# USB_UART.net
KiCad netlist of a schematic drawn in Altium Designer
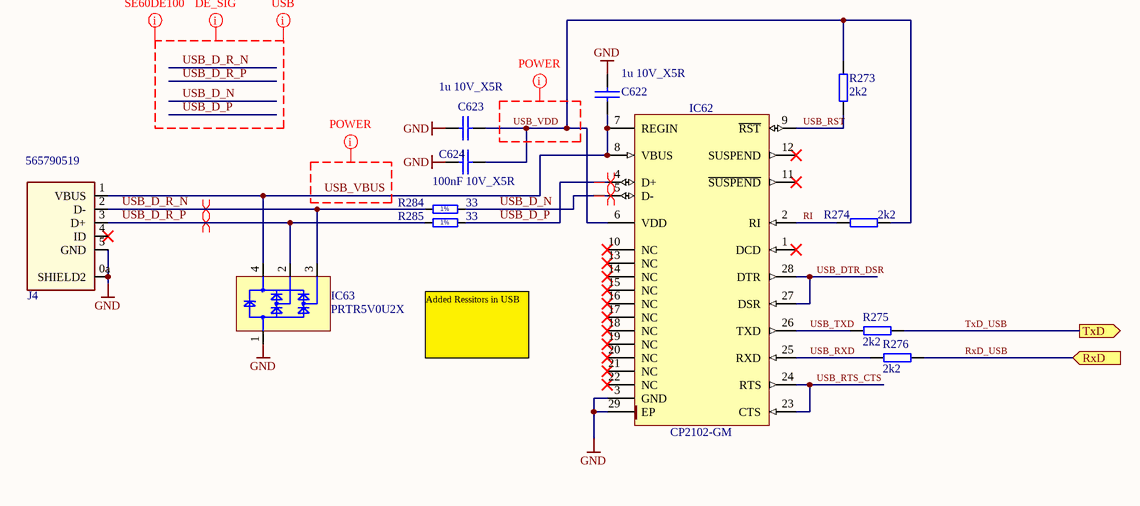
[diagram p0: USB_UART.SchDoc]

(export (version "E")
  (design (tool "Eeschema 10.0.6"))
  (components
    (comp (ref "C622")
      (value "1u 10V_X5R")
      (footprint "0603C")
      (description "Capacitor SMD")
      (libsource (lib "LIBRARY_SCH") (part "CAP_SMD_0603"))
    )
    (comp (ref "C623")
      (value "1u 10V_X5R")
      (footprint "0603C")
      (description "Capacitor SMD")
      (libsource (lib "LIBRARY_SCH") (part "CAP_SMD_0603"))
    )
    (comp (ref "C624")
      (value "100nF 10V_X5R")
      (footprint "0402C")
      (description "Capacitor SMD")
      (libsource (lib "LIBRARY_SCH") (part "CAP_SMD_0402"))
    )
    (comp (ref "IC62")
      (value "CP2102-GM")
      (footprint "QFN50P500X500X100-29N-S335")
      (description "Single-Chip USB to UART Bridge")
      (fields (field (name "MANUFACTURER") "SILICON LABS") (field (name "AUTHOR") "CERN DEM JLC"))
      (libsource (lib "ICs And Semiconductors") (part "CP2102-GM"))
    )
    (comp (ref "IC63")
      (value "PRTR5V0U2X")
      (footprint "sot143b")
      (description "dual 5.5 ESD transient voltage suppressor")
      (libsource (lib "LIBRARY_SCH") (part "D_TVS_PRTR5V0U2X"))
    )
    (comp (ref "J4")
      (value "565790519")
      (footprint "CON_USB_565790519")
      (description "USB mini B connector (Molex)")
      (fields (field (name "PART NUMBER") "10133"))
      (libsource (lib "LIBRARY_SCH") (part "CON_USB_B_MINI_TH"))
    )
    (comp (ref "R273")
      (value "2k2")
      (footprint "0402R")
      (description "SMD Resistor")
      (libsource (lib "LIBRARY_SCH") (part "RES_0402"))
    )
    (comp (ref "R274")
      (value "2k2")
      (footprint "0402R")
      (description "SMD Resistor")
      (libsource (lib "LIBRARY_SCH") (part "RES_0402"))
    )
    (comp (ref "R275")
      (value "2k2")
      (footprint "0402R")
      (description "SMD Resistor")
      (libsource (lib "LIBRARY_SCH") (part "RES_0402"))
    )
    (comp (ref "R276")
      (value "2k2")
      (footprint "0402R")
      (description "SMD Resistor")
      (libsource (lib "LIBRARY_SCH") (part "RES_0402"))
    )
    (comp (ref "R284")
      (value "33")
      (footprint "RESC1005X40N")
      (description "Resistor - 1%")
      (fields
        (field (name "PART NUMBER") "R0402_33R_1%_0.0625W_100PPM")
        (field (name "POWER") "0.0625W")
        (field (name "AUTHOR") "CERN DEM JLC")
      )
      (libsource (lib "Resistors") (part "Resistor - 1%"))
    )
    (comp (ref "R285")
      (value "33")
      (footprint "RESC1005X40N")
      (description "Resistor - 1%")
      (fields
        (field (name "PART NUMBER") "R0402_33R_1%_0.0625W_100PPM")
        (field (name "POWER") "0.0625W")
        (field (name "AUTHOR") "CERN DEM JLC")
      )
      (libsource (lib "Resistors") (part "Resistor - 1%"))
    )
  )
  (nets
    (net (code "1") (name "/RI") (class "Default")
      (node (ref "IC62") (pin "2") (pinfunction "RI_2") (pintype "input"))
      (node (ref "R274") (pin "1") (pinfunction "1_1") (pintype "passive"))
    )
    (net (code "2") (name "/RxD_USB") (class "Default")
      (node (ref "R276") (pin "1") (pinfunction "1_1") (pintype "passive"))
    )
    (net (code "3") (name "/TxD_USB") (class "Default")
      (node (ref "R275") (pin "1") (pinfunction "1_1") (pintype "passive"))
    )
    (net (code "4") (name "/USB_DTR_DSR") (class "Default")
      (node (ref "IC62") (pin "27") (pinfunction "DSR_27") (pintype "input"))
      (node (ref "IC62") (pin "28") (pinfunction "DTR_28") (pintype "output"))
    )
    (net (code "5") (name "/USB_D_N") (class "Default")
      (node (ref "IC62") (pin "5") (pinfunction "D-_5") (pintype "bidirectional"))
      (node (ref "R284") (pin "2") (pinfunction "2_2") (pintype "passive"))
    )
    (net (code "6") (name "/USB_D_P") (class "Default")
      (node (ref "IC62") (pin "4") (pinfunction "D+_4") (pintype "bidirectional"))
      (node (ref "R285") (pin "2") (pinfunction "2_2") (pintype "passive"))
    )
    (net (code "7") (name "/USB_D_R_N") (class "Default")
      (node (ref "IC63") (pin "3") (pinfunction "3_3") (pintype "passive"))
      (node (ref "J4") (pin "2") (pinfunction "D-_2") (pintype "passive"))
      (node (ref "R284") (pin "1") (pinfunction "1_1") (pintype "passive"))
    )
    (net (code "8") (name "/USB_D_R_P") (class "Default")
      (node (ref "IC63") (pin "2") (pinfunction "2_2") (pintype "passive"))
      (node (ref "J4") (pin "3") (pinfunction "D+_3") (pintype "passive"))
      (node (ref "R285") (pin "1") (pinfunction "1_1") (pintype "passive"))
    )
    (net (code "9") (name "/USB_RST") (class "Default")
      (node (ref "IC62") (pin "9") (pinfunction "~{RST}_9") (pintype "bidirectional"))
      (node (ref "R273") (pin "1") (pinfunction "1_1") (pintype "passive"))
    )
    (net (code "10") (name "/USB_RTS_CTS") (class "Default")
      (node (ref "IC62") (pin "23") (pinfunction "CTS_23") (pintype "input"))
      (node (ref "IC62") (pin "24") (pinfunction "RTS_24") (pintype "output"))
    )
    (net (code "11") (name "/USB_RXD") (class "Default")
      (node (ref "IC62") (pin "25") (pinfunction "RXD_25") (pintype "input"))
      (node (ref "R276") (pin "2") (pinfunction "2_2") (pintype "passive"))
    )
    (net (code "12") (name "/USB_TXD") (class "Default")
      (node (ref "IC62") (pin "26") (pinfunction "TXD_26") (pintype "output"))
      (node (ref "R275") (pin "2") (pinfunction "2_2") (pintype "passive"))
    )
    (net (code "13") (name "/USB_VBUS") (class "Default")
      (node (ref "C622") (pin "2") (pinfunction "2_2") (pintype "passive"))
      (node (ref "IC62") (pin "7") (pinfunction "REGIN_7") (pintype "power_in"))
      (node (ref "IC62") (pin "8") (pinfunction "VBUS_8") (pintype "input"))
      (node (ref "IC63") (pin "4") (pinfunction "4_4") (pintype "passive"))
      (node (ref "J4") (pin "1") (pinfunction "VBUS_1") (pintype "passive"))
    )
    (net (code "14") (name "/USB_VDD") (class "Default")
      (node (ref "C623") (pin "2") (pinfunction "2_2") (pintype "passive"))
      (node (ref "C624") (pin "2") (pinfunction "2_2") (pintype "passive"))
      (node (ref "IC62") (pin "6") (pinfunction "VDD_6") (pintype "power_in"))
      (node (ref "R273") (pin "2") (pinfunction "2_2") (pintype "passive"))
      (node (ref "R274") (pin "2") (pinfunction "2_2") (pintype "passive"))
    )
    (net (code "15") (name "GND") (class "Default")
      (node (ref "C622") (pin "1") (pinfunction "1_1") (pintype "passive"))
      (node (ref "C623") (pin "1") (pinfunction "1_1") (pintype "passive"))
      (node (ref "C624") (pin "1") (pinfunction "1_1") (pintype "passive"))
      (node (ref "IC62") (pin "29") (pinfunction "EP_29") (pintype "power_in"))
      (node (ref "IC62") (pin "3") (pinfunction "GND_3") (pintype "power_in"))
      (node (ref "IC63") (pin "1") (pinfunction "1_1") (pintype "passive"))
      (node (ref "J4") (pin "0") (pinfunction "SHIELD2_0") (pintype "passive"))
      (node (ref "J4") (pin "0a") (pinfunction "SHIELD2_0a") (pintype "passive"))
      (node (ref "J4") (pin "5") (pinfunction "GND_5") (pintype "passive"))
    )
    (net (code "16") (name "unconnected-(IC62-DCD-Pad1)") (class "Default")
      (node (ref "IC62") (pin "1") (pinfunction "DCD_1") (pintype "input+no_connect"))
    )
    (net (code "17") (name "unconnected-(IC62-NC-Pad10)") (class "Default")
      (node (ref "IC62") (pin "10") (pinfunction "NC_10") (pintype "passive+no_connect"))
    )
    (net (code "18") (name "unconnected-(IC62-NC-Pad13)") (class "Default")
      (node (ref "IC62") (pin "13") (pinfunction "NC_13") (pintype "passive+no_connect"))
    )
    (net (code "19") (name "unconnected-(IC62-NC-Pad14)") (class "Default")
      (node (ref "IC62") (pin "14") (pinfunction "NC_14") (pintype "passive+no_connect"))
    )
    (net (code "20") (name "unconnected-(IC62-NC-Pad15)") (class "Default")
      (node (ref "IC62") (pin "15") (pinfunction "NC_15") (pintype "passive+no_connect"))
    )
    (net (code "21") (name "unconnected-(IC62-NC-Pad16)") (class "Default")
      (node (ref "IC62") (pin "16") (pinfunction "NC_16") (pintype "passive+no_connect"))
    )
    (net (code "22") (name "unconnected-(IC62-NC-Pad17)") (class "Default")
      (node (ref "IC62") (pin "17") (pinfunction "NC_17") (pintype "passive+no_connect"))
    )
    (net (code "23") (name "unconnected-(IC62-NC-Pad18)") (class "Default")
      (node (ref "IC62") (pin "18") (pinfunction "NC_18") (pintype "passive+no_connect"))
    )
    (net (code "24") (name "unconnected-(IC62-NC-Pad19)") (class "Default")
      (node (ref "IC62") (pin "19") (pinfunction "NC_19") (pintype "passive+no_connect"))
    )
    (net (code "25") (name "unconnected-(IC62-NC-Pad20)") (class "Default")
      (node (ref "IC62") (pin "20") (pinfunction "NC_20") (pintype "passive+no_connect"))
    )
    (net (code "26") (name "unconnected-(IC62-NC-Pad21)") (class "Default")
      (node (ref "IC62") (pin "21") (pinfunction "NC_21") (pintype "passive+no_connect"))
    )
    (net (code "27") (name "unconnected-(IC62-NC-Pad22)") (class "Default")
      (node (ref "IC62") (pin "22") (pinfunction "NC_22") (pintype "passive+no_connect"))
    )
    (net (code "28") (name "unconnected-(IC62-SUSPEND-Pad12)") (class "Default")
      (node (ref "IC62") (pin "12") (pinfunction "SUSPEND_12") (pintype "output+no_connect"))
    )
    (net (code "29") (name "unconnected-(IC62-~{SUSPEND}-Pad11)") (class "Default")
      (node (ref "IC62") (pin "11") (pinfunction "~{SUSPEND}_11") (pintype "output+no_connect"))
    )
    (net (code "30") (name "unconnected-(J4-ID-Pad4)") (class "Default")
      (node (ref "J4") (pin "4") (pinfunction "ID_4") (pintype "passive+no_connect"))
    )
  )
)
